# KMO_IO_MV1_1a.net
KiCad netlist of a schematic drawn in EAGLE
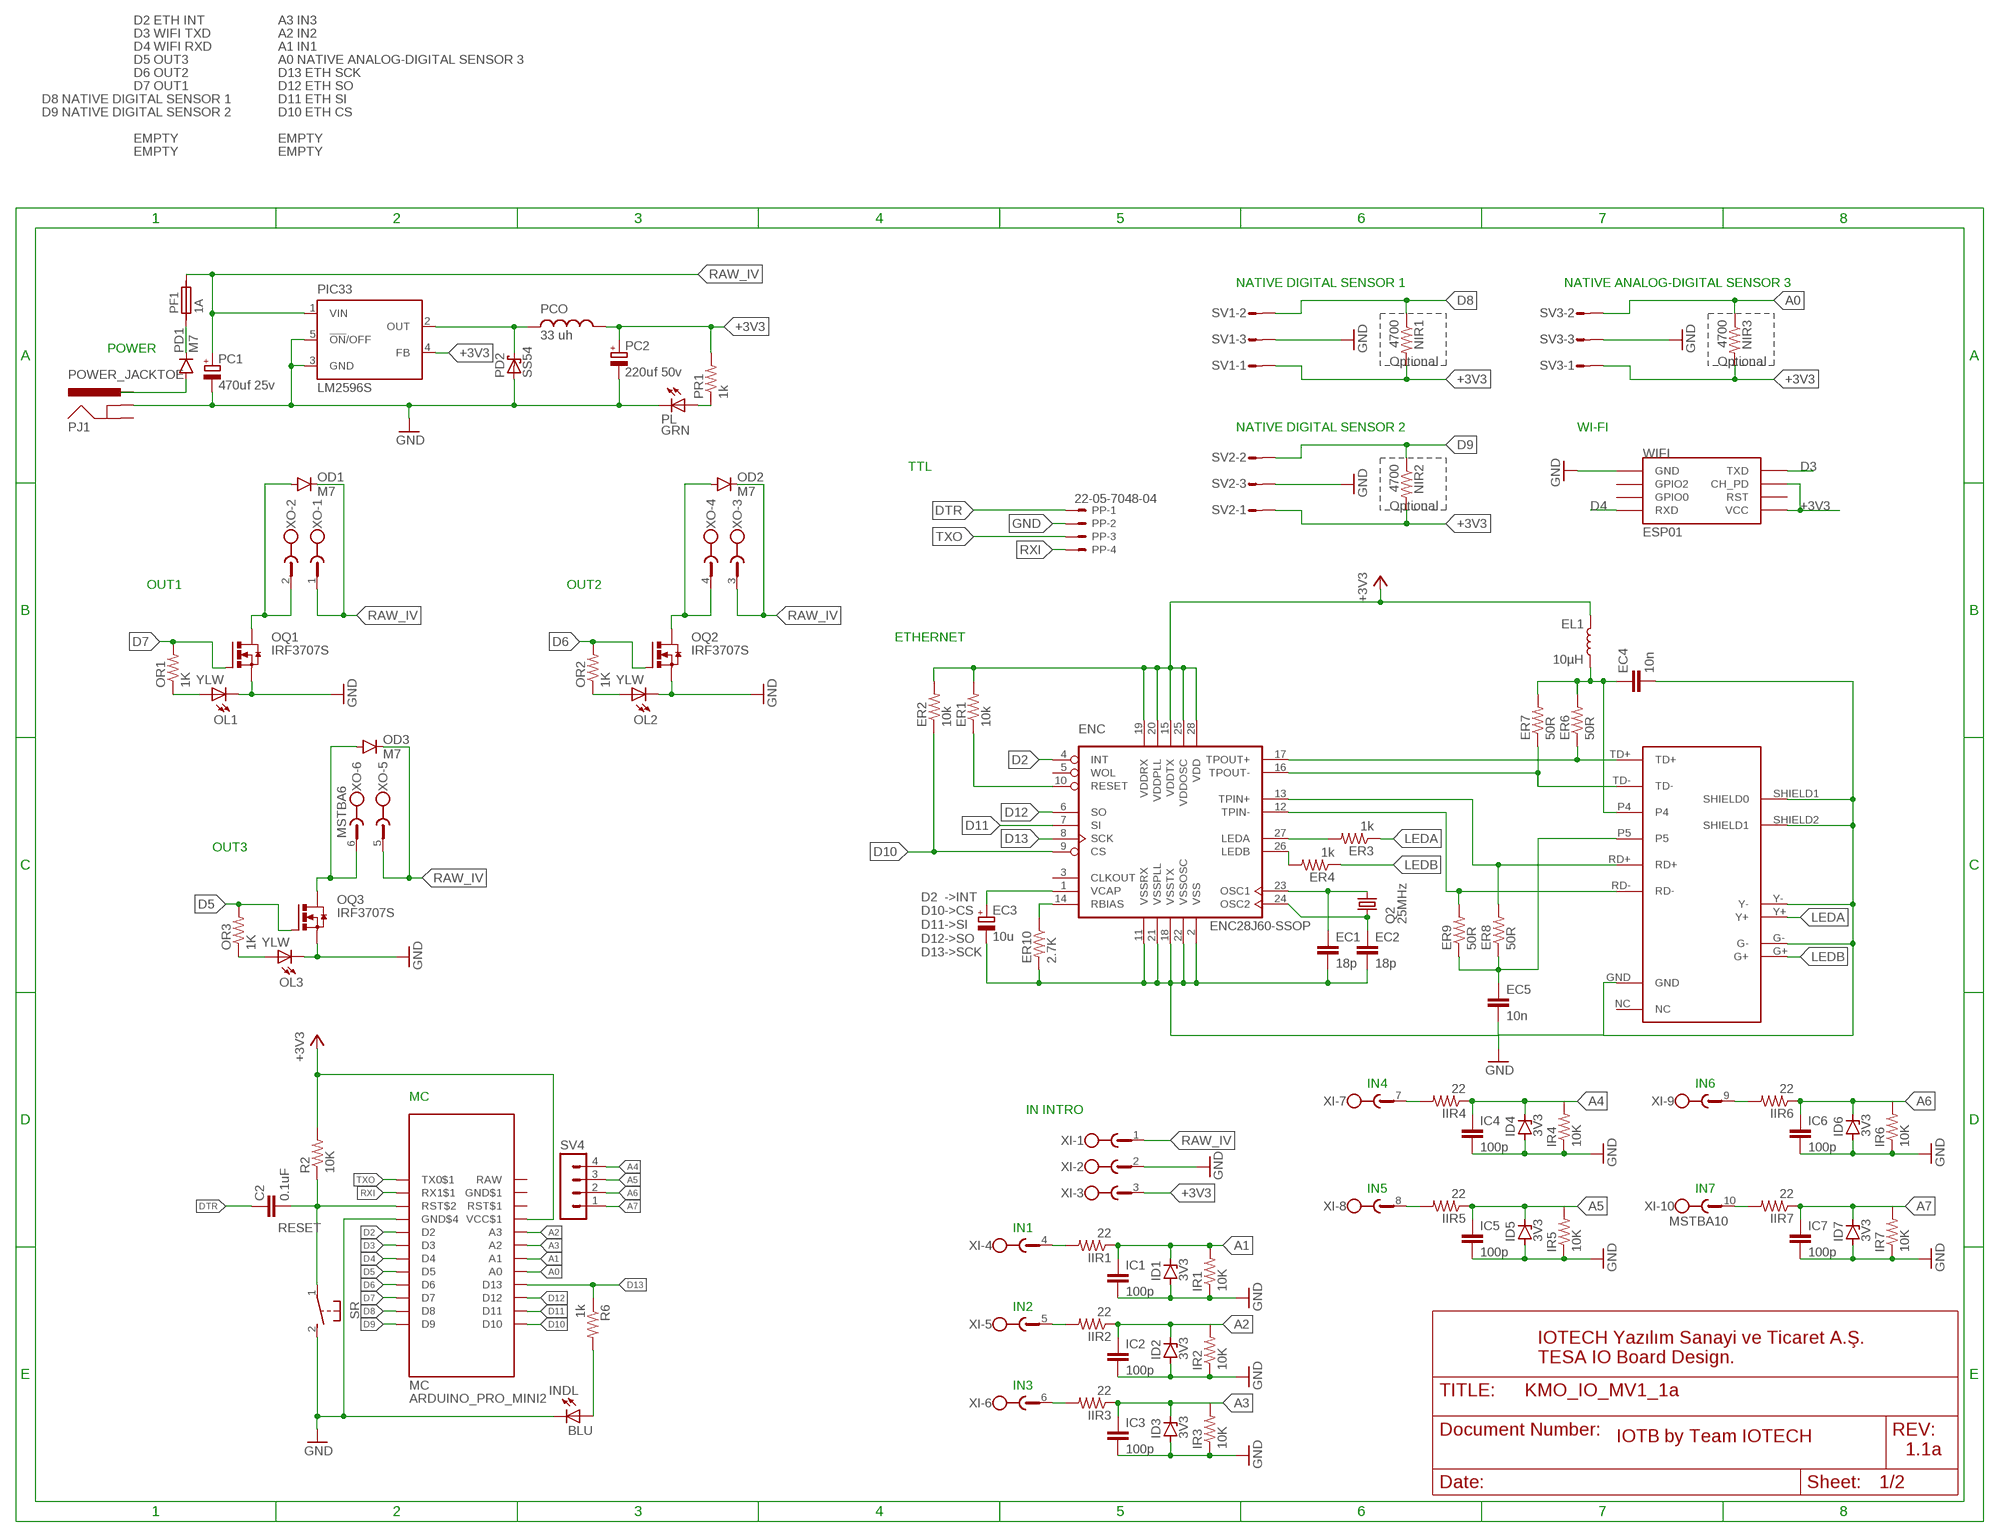
[diagram p0: schematic, sheet 1]
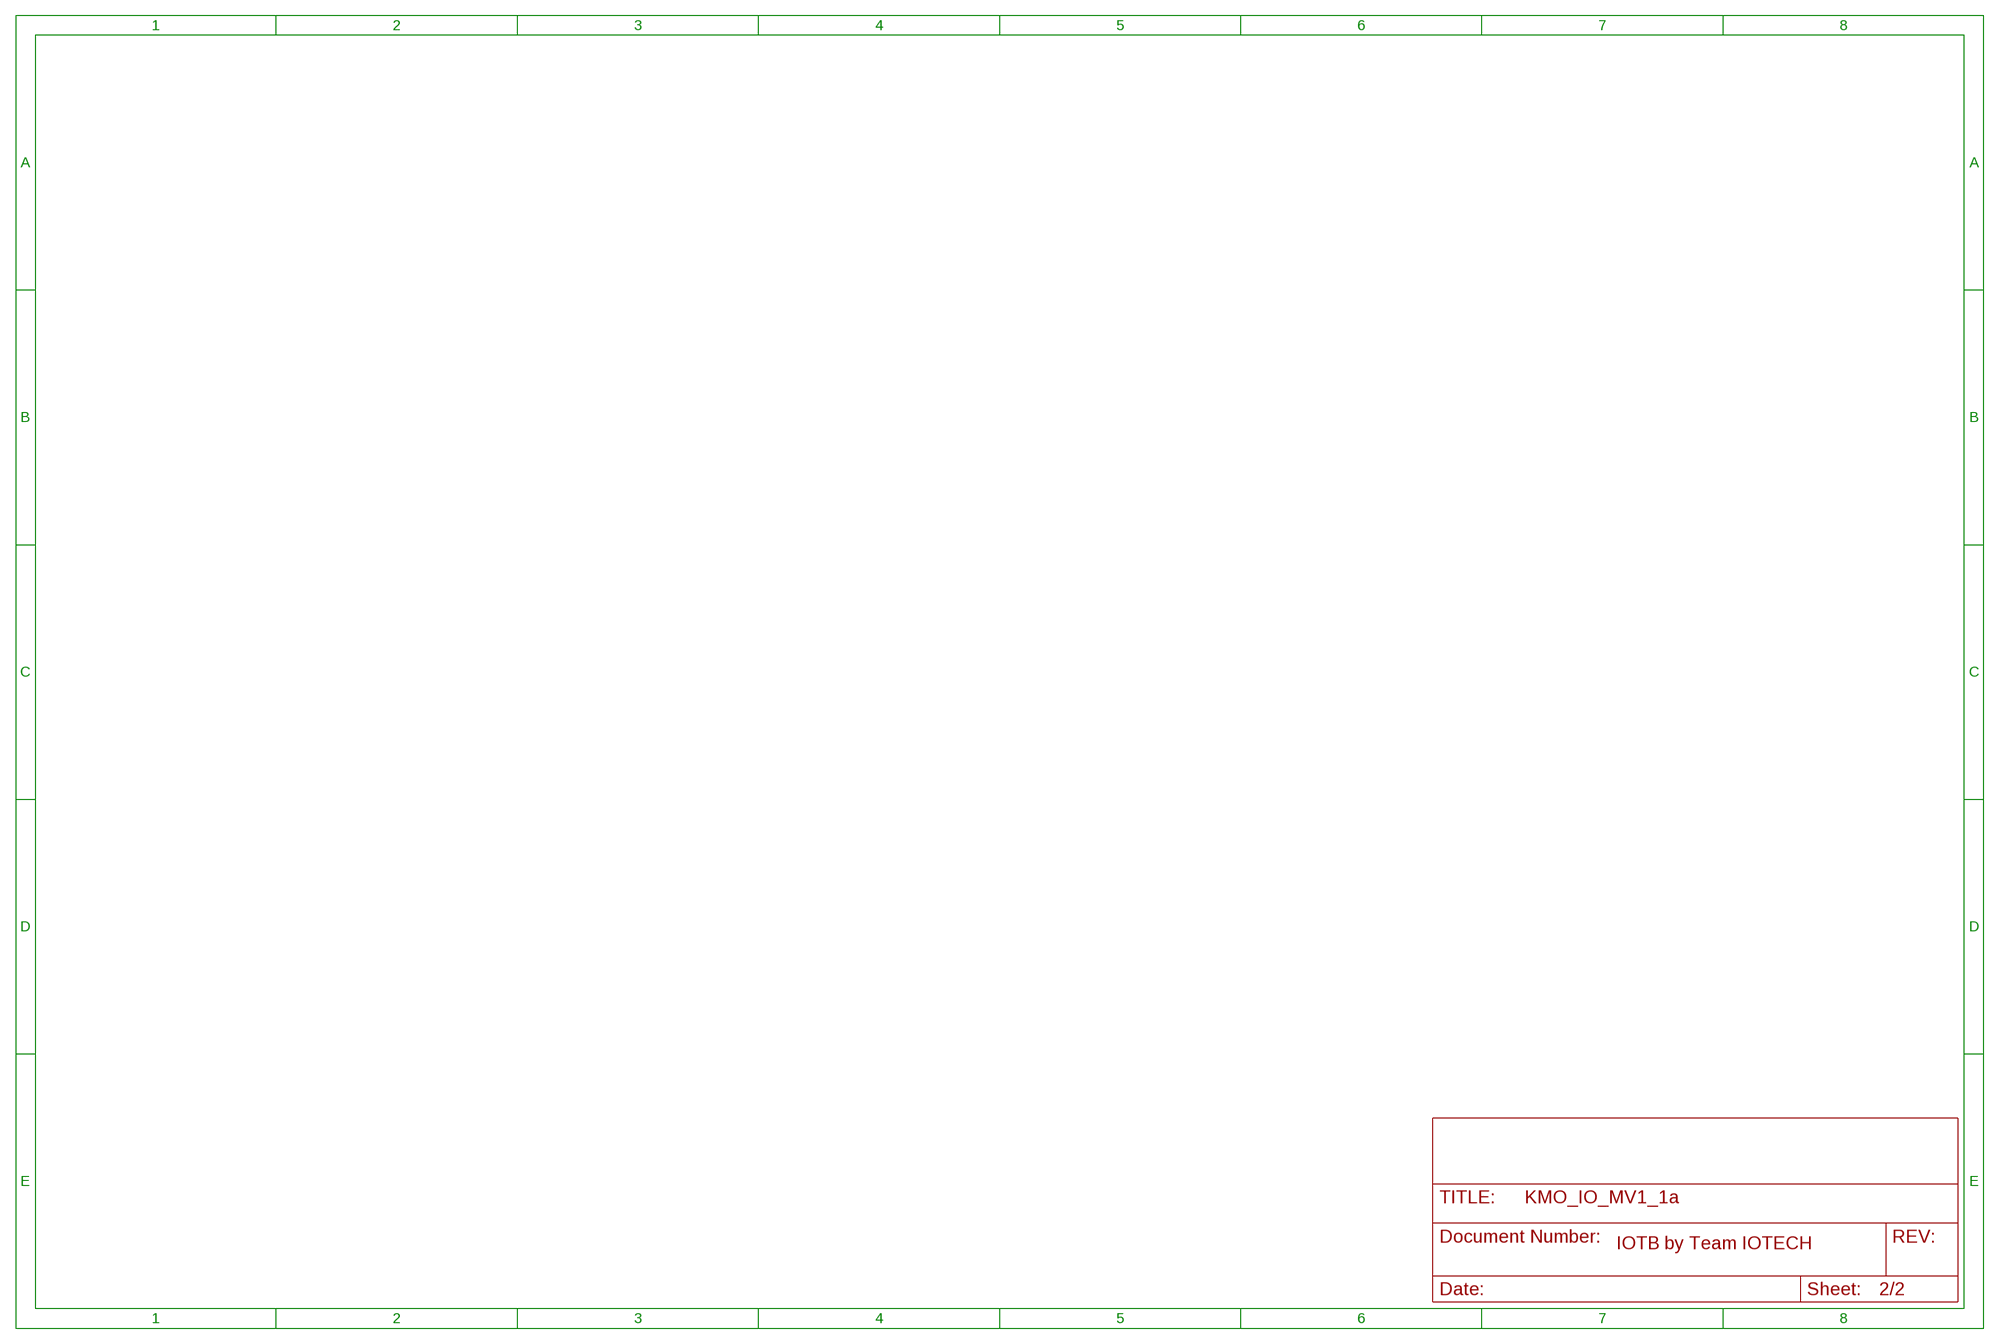
[diagram p1: schematic, sheet 2]

(export (version "E")
  (design (tool "Eeschema 10.0.6"))
  (components
    (comp (ref "C2")
      (value "0.1uF")
      (footprint "eagle-import:0805")
      (libsource (lib "eagle-import") (part "CAP0805"))
    )
    (comp (ref "EC1")
      (value "18p")
      (footprint "eagle-import:0805")
      (libsource (lib "eagle-import") (part "CAP0805"))
    )
    (comp (ref "EC2")
      (value "18p")
      (footprint "eagle-import:0805")
      (libsource (lib "eagle-import") (part "CAP0805"))
    )
    (comp (ref "EC3")
      (value "10u")
      (footprint "eagle-import:CT3216")
      (libsource (lib "eagle-import") (part "CPOL-EUCT3216"))
    )
    (comp (ref "EC4")
      (value "10n")
      (footprint "eagle-import:0805")
      (libsource (lib "eagle-import") (part "CAP0805"))
    )
    (comp (ref "EC5")
      (value "10n")
      (footprint "eagle-import:0805")
      (libsource (lib "eagle-import") (part "CAP0805"))
    )
    (comp (ref "EL1")
      (value "10µH")
      (footprint "eagle-import:0805")
      (libsource (lib "eagle-import") (part "INDUCTOR-0805-3.3UH"))
    )
    (comp (ref "ENC")
      (value "ENC28J60-SSOP")
      (footprint "eagle-import:SSOP28")
      (libsource (lib "eagle-import") (part "ENC28J60-SSOP"))
    )
    (comp (ref "ER1")
      (value "10k")
      (footprint "eagle-import:0805")
      (libsource (lib "eagle-import") (part "RESISTOR0805-RES"))
    )
    (comp (ref "ER2")
      (value "10k")
      (footprint "eagle-import:0805")
      (libsource (lib "eagle-import") (part "RESISTOR0805-RES"))
    )
    (comp (ref "ER3")
      (value "1k")
      (footprint "eagle-import:0805")
      (libsource (lib "eagle-import") (part "RESISTOR0805-RES"))
    )
    (comp (ref "ER4")
      (value "1k")
      (footprint "eagle-import:0805")
      (libsource (lib "eagle-import") (part "RESISTOR0805-RES"))
    )
    (comp (ref "ER6")
      (value "50R")
      (footprint "eagle-import:0805")
      (libsource (lib "eagle-import") (part "RESISTOR0805-RES"))
    )
    (comp (ref "ER7")
      (value "50R")
      (footprint "eagle-import:0805")
      (libsource (lib "eagle-import") (part "RESISTOR0805-RES"))
    )
    (comp (ref "ER8")
      (value "50R")
      (footprint "eagle-import:0805")
      (libsource (lib "eagle-import") (part "RESISTOR0805-RES"))
    )
    (comp (ref "ER9")
      (value "50R")
      (footprint "eagle-import:0805")
      (libsource (lib "eagle-import") (part "RESISTOR0805-RES"))
    )
    (comp (ref "ER10")
      (value "2.7K")
      (footprint "eagle-import:0805")
      (libsource (lib "eagle-import") (part "RESISTOR0805-RES"))
    )
    (comp (ref "IC1")
      (value "100p")
      (footprint "eagle-import:0805")
      (libsource (lib "eagle-import") (part "CAP0805"))
    )
    (comp (ref "IC2")
      (value "100p")
      (footprint "eagle-import:0805")
      (libsource (lib "eagle-import") (part "CAP0805"))
    )
    (comp (ref "IC3")
      (value "100p")
      (footprint "eagle-import:0805")
      (libsource (lib "eagle-import") (part "CAP0805"))
    )
    (comp (ref "IC4")
      (value "100p")
      (footprint "eagle-import:0805")
      (libsource (lib "eagle-import") (part "CAP0805"))
    )
    (comp (ref "IC5")
      (value "100p")
      (footprint "eagle-import:0805")
      (libsource (lib "eagle-import") (part "CAP0805"))
    )
    (comp (ref "IC6")
      (value "100p")
      (footprint "eagle-import:0805")
      (libsource (lib "eagle-import") (part "CAP0805"))
    )
    (comp (ref "IC7")
      (value "100p")
      (footprint "eagle-import:0805")
      (libsource (lib "eagle-import") (part "CAP0805"))
    )
    (comp (ref "ID1")
      (value "3V3")
      (footprint "eagle-import:SOT23")
      (libsource (lib "eagle-import") (part "ZENER-DIODESOT23"))
    )
    (comp (ref "ID2")
      (value "3V3")
      (footprint "eagle-import:SOT23")
      (libsource (lib "eagle-import") (part "ZENER-DIODESOT23"))
    )
    (comp (ref "ID3")
      (value "3V3")
      (footprint "eagle-import:SOT23")
      (libsource (lib "eagle-import") (part "ZENER-DIODESOT23"))
    )
    (comp (ref "ID4")
      (value "3V3")
      (footprint "eagle-import:SOT23")
      (libsource (lib "eagle-import") (part "ZENER-DIODESOT23"))
    )
    (comp (ref "ID5")
      (value "3V3")
      (footprint "eagle-import:SOT23")
      (libsource (lib "eagle-import") (part "ZENER-DIODESOT23"))
    )
    (comp (ref "ID6")
      (value "3V3")
      (footprint "eagle-import:SOT23")
      (libsource (lib "eagle-import") (part "ZENER-DIODESOT23"))
    )
    (comp (ref "ID7")
      (value "3V3")
      (footprint "eagle-import:SOT23")
      (libsource (lib "eagle-import") (part "ZENER-DIODESOT23"))
    )
    (comp (ref "IIR1")
      (value "22")
      (footprint "eagle-import:0805")
      (libsource (lib "eagle-import") (part "RESISTOR0805-RES"))
    )
    (comp (ref "IIR2")
      (value "22")
      (footprint "eagle-import:0805")
      (libsource (lib "eagle-import") (part "RESISTOR0805-RES"))
    )
    (comp (ref "IIR3")
      (value "22")
      (footprint "eagle-import:0805")
      (libsource (lib "eagle-import") (part "RESISTOR0805-RES"))
    )
    (comp (ref "IIR4")
      (value "22")
      (footprint "eagle-import:0805")
      (libsource (lib "eagle-import") (part "RESISTOR0805-RES"))
    )
    (comp (ref "IIR5")
      (value "22")
      (footprint "eagle-import:0805")
      (libsource (lib "eagle-import") (part "RESISTOR0805-RES"))
    )
    (comp (ref "IIR6")
      (value "22")
      (footprint "eagle-import:0805")
      (libsource (lib "eagle-import") (part "RESISTOR0805-RES"))
    )
    (comp (ref "IIR7")
      (value "22")
      (footprint "eagle-import:0805")
      (libsource (lib "eagle-import") (part "RESISTOR0805-RES"))
    )
    (comp (ref "INDL")
      (value "BLU")
      (footprint "eagle-import:CHIP-LED0805")
      (libsource (lib "eagle-import") (part "LEDCHIP-LED0805"))
    )
    (comp (ref "IR1")
      (value "10K")
      (footprint "eagle-import:0805")
      (libsource (lib "eagle-import") (part "RESISTOR0805-RES"))
    )
    (comp (ref "IR2")
      (value "10K")
      (footprint "eagle-import:0805")
      (libsource (lib "eagle-import") (part "RESISTOR0805-RES"))
    )
    (comp (ref "IR3")
      (value "10K")
      (footprint "eagle-import:0805")
      (libsource (lib "eagle-import") (part "RESISTOR0805-RES"))
    )
    (comp (ref "IR4")
      (value "10K")
      (footprint "eagle-import:0805")
      (libsource (lib "eagle-import") (part "RESISTOR0805-RES"))
    )
    (comp (ref "IR5")
      (value "10K")
      (footprint "eagle-import:0805")
      (libsource (lib "eagle-import") (part "RESISTOR0805-RES"))
    )
    (comp (ref "IR6")
      (value "10K")
      (footprint "eagle-import:0805")
      (libsource (lib "eagle-import") (part "RESISTOR0805-RES"))
    )
    (comp (ref "IR7")
      (value "10K")
      (footprint "eagle-import:0805")
      (libsource (lib "eagle-import") (part "RESISTOR0805-RES"))
    )
    (comp (ref "MC")
      (value "ARDUINO_PRO_MINI2")
      (footprint "eagle-import:ARDUINO_PRO_MINI2")
      (libsource (lib "eagle-import") (part "ARDUINO_PRO_MINI2"))
    )
    (comp (ref "NIR1")
      (value "4700")
      (footprint "eagle-import:0805")
      (libsource (lib "eagle-import") (part "RESISTOR0805-RES"))
    )
    (comp (ref "NIR2")
      (value "4700")
      (footprint "eagle-import:0805")
      (libsource (lib "eagle-import") (part "RESISTOR0805-RES"))
    )
    (comp (ref "NIR3")
      (value "4700")
      (footprint "eagle-import:0805")
      (libsource (lib "eagle-import") (part "RESISTOR0805-RES"))
    )
    (comp (ref "OD1")
      (value "M7")
      (footprint "eagle-import:SMA-DIODE")
      (libsource (lib "eagle-import") (part "DIODESMA"))
    )
    (comp (ref "OD2")
      (value "M7")
      (footprint "eagle-import:SMA-DIODE")
      (libsource (lib "eagle-import") (part "DIODESMA"))
    )
    (comp (ref "OD3")
      (value "M7")
      (footprint "eagle-import:SMA-DIODE")
      (libsource (lib "eagle-import") (part "DIODESMA"))
    )
    (comp (ref "OL1")
      (value "YLW")
      (footprint "eagle-import:CHIP-LED0805")
      (libsource (lib "eagle-import") (part "LEDCHIP-LED0805"))
    )
    (comp (ref "OL2")
      (value "YLW")
      (footprint "eagle-import:CHIP-LED0805")
      (libsource (lib "eagle-import") (part "LEDCHIP-LED0805"))
    )
    (comp (ref "OL3")
      (value "YLW")
      (footprint "eagle-import:CHIP-LED0805")
      (libsource (lib "eagle-import") (part "LEDCHIP-LED0805"))
    )
    (comp (ref "OQ1")
      (value "IRF3707S")
      (footprint "eagle-import:D2PACK")
      (libsource (lib "eagle-import") (part "IRF3704S"))
    )
    (comp (ref "OQ2")
      (value "IRF3707S")
      (footprint "eagle-import:D2PACK")
      (libsource (lib "eagle-import") (part "IRF3704S"))
    )
    (comp (ref "OQ3")
      (value "IRF3707S")
      (footprint "eagle-import:D2PACK")
      (libsource (lib "eagle-import") (part "IRF3704S"))
    )
    (comp (ref "OR1")
      (value "1K")
      (footprint "eagle-import:0805")
      (libsource (lib "eagle-import") (part "RESISTOR0805-RES"))
    )
    (comp (ref "OR2")
      (value "1K")
      (footprint "eagle-import:0805")
      (libsource (lib "eagle-import") (part "RESISTOR0805-RES"))
    )
    (comp (ref "OR3")
      (value "1K")
      (footprint "eagle-import:0805")
      (libsource (lib "eagle-import") (part "RESISTOR0805-RES"))
    )
    (comp (ref "PC1")
      (value "470uf 25v")
      (footprint "eagle-import:140CLH-1010")
      (libsource (lib "eagle-import") (part "CPOL-EU140CLH-1010"))
    )
    (comp (ref "PC2")
      (value "220uf 50v")
      (footprint "eagle-import:140CLH-1010")
      (libsource (lib "eagle-import") (part "CPOL-EU140CLH-1010"))
    )
    (comp (ref "PCO")
      (value "33 uh")
      (footprint "eagle-import:MSS1260")
      (libsource (lib "eagle-import") (part "MSS1260"))
    )
    (comp (ref "PD1")
      (value "M7")
      (footprint "eagle-import:SMA-DIODE")
      (libsource (lib "eagle-import") (part "DIODESMA"))
    )
    (comp (ref "PD2")
      (value "SS54")
      (footprint "eagle-import:SMB")
      (libsource (lib "eagle-import") (part "SCHOTTKY-DIODESMD"))
    )
    (comp (ref "PF1")
      (value "1A")
      (footprint "eagle-import:1820")
      (libsource (lib "eagle-import") (part "SIBA194600"))
    )
    (comp (ref "PIC33")
      (value "LM2596S")
      (footprint "eagle-import:TO263-5")
      (fields (field (name "MF") "NATIONAL SEMICONDUCTOR") (field (name "MPN") "LM2596S-ADJ/NOPB"))
      (libsource (lib "eagle-import") (part "LM2596S"))
    )
    (comp (ref "PJ1")
      (value "POWER_JACKTOE")
      (footprint "eagle-import:POWER_JACK_SMD_OVERPASTE_TOE")
      (libsource (lib "eagle-import") (part "POWER_JACKTOE"))
    )
    (comp (ref "PL")
      (value "GRN")
      (footprint "eagle-import:CHIP-LED0805")
      (libsource (lib "eagle-import") (part "LEDCHIP-LED0805"))
    )
    (comp (ref "PP")
      (value "22-05-7048-04")
      (footprint "eagle-import:7395-04")
      (fields (field (name "MF") "MOLEX"))
      (libsource (lib "eagle-import") (part "22-?-0405-7048"))
    )
    (comp (ref "PR1")
      (value "1k")
      (footprint "eagle-import:0805")
      (libsource (lib "eagle-import") (part "RESISTOR0805-RES"))
    )
    (comp (ref "Q2")
      (value "25MHz")
      (footprint "eagle-import:5.0X3.2_2")
      (libsource (lib "eagle-import") (part "KX-9B"))
    )
    (comp (ref "R2")
      (value "10K")
      (footprint "eagle-import:0805")
      (libsource (lib "eagle-import") (part "RESISTOR0805-RES"))
    )
    (comp (ref "R6")
      (value "1k")
      (footprint "eagle-import:0805")
      (libsource (lib "eagle-import") (part "RESISTOR0805-RES"))
    )
    (comp (ref "SR")
      (value "31-XX")
      (footprint "eagle-import:B3F-31XX")
      (fields (field (name "MPN") "B3F-3100"))
      (libsource (lib "eagle-import") (part "31-XX"))
    )
    (comp (ref "SV1")
      (value "S03P")
      (footprint "eagle-import:S03P")
      (libsource (lib "eagle-import") (part "S03P"))
    )
    (comp (ref "SV2")
      (value "S03P")
      (footprint "eagle-import:S03P")
      (libsource (lib "eagle-import") (part "S03P"))
    )
    (comp (ref "SV3")
      (value "S03P")
      (footprint "eagle-import:S03P")
      (libsource (lib "eagle-import") (part "S03P"))
    )
    (comp (ref "SV4")
      (value "MA04-1")
      (footprint "eagle-import:MA04-1")
      (libsource (lib "eagle-import") (part "MA04-1"))
    )
    (comp (ref "U$2")
      (value "HR911105A")
      (footprint "eagle-import:RJ45")
      (libsource (lib "eagle-import") (part "HR911105A"))
    )
    (comp (ref "WIFI")
      (value "ESP01")
      (footprint "eagle-import:ESP01")
      (libsource (lib "eagle-import") (part "ESP01"))
    )
    (comp (ref "XI")
      (value "MSTBA10")
      (footprint "eagle-import:MSTBA10")
      (fields (field (name "MF") "FARNELL") (field (name "MPN") "1757323"))
      (libsource (lib "eagle-import") (part "MSTBA10"))
    )
    (comp (ref "XO")
      (value "MSTBA6")
      (footprint "eagle-import:MSTBA6")
      (fields (field (name "MF") "FARNELL") (field (name "MPN") "1757284"))
      (libsource (lib "eagle-import") (part "MSTBA6"))
    )
  )
  (nets
    (net (code "1") (name "+3V3") (class "Default")
      (node (ref "EL1") (pin "1") (pinfunction "1_1") (pintype "passive"))
      (node (ref "ENC") (pin "15") (pinfunction "VDDTX_15") (pintype "power_in"))
      (node (ref "ENC") (pin "19") (pinfunction "VDDRX_19") (pintype "power_in"))
      (node (ref "ENC") (pin "20") (pinfunction "VDDPLL_20") (pintype "power_in"))
      (node (ref "ENC") (pin "25") (pinfunction "VDDOSC_25") (pintype "power_in"))
      (node (ref "ENC") (pin "28") (pinfunction "VDD_28") (pintype "power_in"))
      (node (ref "ER1") (pin "2") (pinfunction "2_2") (pintype "passive"))
      (node (ref "ER2") (pin "2") (pinfunction "2_2") (pintype "passive"))
      (node (ref "MC") (pin "VCC$1") (pinfunction "VCC$1_VCC$1") (pintype "power_in"))
      (node (ref "NIR1") (pin "2") (pinfunction "2_2") (pintype "passive"))
      (node (ref "NIR2") (pin "2") (pinfunction "2_2") (pintype "passive"))
      (node (ref "NIR3") (pin "2") (pinfunction "2_2") (pintype "passive"))
      (node (ref "PC2") (pin "+") (pinfunction "+_+") (pintype "passive"))
      (node (ref "PCO") (pin "P$1") (pinfunction "P$1_P$1") (pintype "passive"))
      (node (ref "PIC33") (pin "4") (pinfunction "FB_4") (pintype "input"))
      (node (ref "PR1") (pin "2") (pinfunction "2_2") (pintype "passive"))
      (node (ref "R2") (pin "2") (pinfunction "2_2") (pintype "passive"))
      (node (ref "SV1") (pin "1") (pinfunction "S_1") (pintype "passive"))
      (node (ref "SV2") (pin "1") (pinfunction "S_1") (pintype "passive"))
      (node (ref "SV3") (pin "1") (pinfunction "S_1") (pintype "passive"))
      (node (ref "WIFI") (pin "CH_PD") (pinfunction "CH_PD_CH_PD") (pintype "bidirectional"))
      (node (ref "WIFI") (pin "VCC") (pinfunction "VCC_VCC") (pintype "bidirectional"))
      (node (ref "XI") (pin "3") (pinfunction "1_3") (pintype "passive"))
    )
    (net (code "2") (name "A0") (class "Default")
      (node (ref "MC") (pin "A0") (pinfunction "A0_A0") (pintype "bidirectional"))
      (node (ref "NIR3") (pin "1") (pinfunction "1_1") (pintype "passive"))
      (node (ref "SV3") (pin "2") (pinfunction "S_2") (pintype "passive"))
    )
    (net (code "3") (name "A1") (class "Default")
      (node (ref "IC1") (pin "1") (pinfunction "1_1") (pintype "passive"))
      (node (ref "ID1") (pin "3") (pinfunction "C_3") (pintype "passive"))
      (node (ref "IIR1") (pin "1") (pinfunction "1_1") (pintype "passive"))
      (node (ref "IR1") (pin "2") (pinfunction "2_2") (pintype "passive"))
      (node (ref "MC") (pin "A1") (pinfunction "A1_A1") (pintype "bidirectional"))
    )
    (net (code "4") (name "A2") (class "Default")
      (node (ref "IC2") (pin "1") (pinfunction "1_1") (pintype "passive"))
      (node (ref "ID2") (pin "3") (pinfunction "C_3") (pintype "passive"))
      (node (ref "IIR2") (pin "1") (pinfunction "1_1") (pintype "passive"))
      (node (ref "IR2") (pin "2") (pinfunction "2_2") (pintype "passive"))
      (node (ref "MC") (pin "A3") (pinfunction "A3_A3") (pintype "bidirectional"))
    )
    (net (code "5") (name "A3") (class "Default")
      (node (ref "IC3") (pin "1") (pinfunction "1_1") (pintype "passive"))
      (node (ref "ID3") (pin "3") (pinfunction "C_3") (pintype "passive"))
      (node (ref "IIR3") (pin "1") (pinfunction "1_1") (pintype "passive"))
      (node (ref "IR3") (pin "2") (pinfunction "2_2") (pintype "passive"))
      (node (ref "MC") (pin "A2") (pinfunction "A2_A2") (pintype "bidirectional"))
    )
    (net (code "6") (name "A4") (class "Default")
      (node (ref "IC4") (pin "1") (pinfunction "1_1") (pintype "passive"))
      (node (ref "ID4") (pin "3") (pinfunction "C_3") (pintype "passive"))
      (node (ref "IIR4") (pin "1") (pinfunction "1_1") (pintype "passive"))
      (node (ref "IR4") (pin "2") (pinfunction "2_2") (pintype "passive"))
      (node (ref "SV4") (pin "4") (pinfunction "4_4") (pintype "passive"))
    )
    (net (code "7") (name "A5") (class "Default")
      (node (ref "IC5") (pin "1") (pinfunction "1_1") (pintype "passive"))
      (node (ref "ID5") (pin "3") (pinfunction "C_3") (pintype "passive"))
      (node (ref "IIR5") (pin "1") (pinfunction "1_1") (pintype "passive"))
      (node (ref "IR5") (pin "2") (pinfunction "2_2") (pintype "passive"))
      (node (ref "SV4") (pin "3") (pinfunction "3_3") (pintype "passive"))
    )
    (net (code "8") (name "A6") (class "Default")
      (node (ref "IC6") (pin "1") (pinfunction "1_1") (pintype "passive"))
      (node (ref "ID6") (pin "3") (pinfunction "C_3") (pintype "passive"))
      (node (ref "IIR6") (pin "1") (pinfunction "1_1") (pintype "passive"))
      (node (ref "IR6") (pin "2") (pinfunction "2_2") (pintype "passive"))
      (node (ref "SV4") (pin "2") (pinfunction "2_2") (pintype "passive"))
    )
    (net (code "9") (name "A7") (class "Default")
      (node (ref "IC7") (pin "1") (pinfunction "1_1") (pintype "passive"))
      (node (ref "ID7") (pin "3") (pinfunction "C_3") (pintype "passive"))
      (node (ref "IIR7") (pin "1") (pinfunction "1_1") (pintype "passive"))
      (node (ref "IR7") (pin "2") (pinfunction "2_2") (pintype "passive"))
      (node (ref "SV4") (pin "1") (pinfunction "1_1") (pintype "passive"))
    )
    (net (code "10") (name "D2") (class "Default")
      (node (ref "ENC") (pin "4") (pinfunction "INT_4") (pintype "output"))
      (node (ref "MC") (pin "D2") (pinfunction "D2_D2") (pintype "bidirectional"))
    )
    (net (code "11") (name "D3") (class "Default")
      (node (ref "MC") (pin "D3") (pinfunction "D3_D3") (pintype "bidirectional"))
      (node (ref "WIFI") (pin "TX") (pinfunction "TXD_TX") (pintype "bidirectional"))
    )
    (net (code "12") (name "D4") (class "Default")
      (node (ref "MC") (pin "D4") (pinfunction "D4_D4") (pintype "bidirectional"))
      (node (ref "WIFI") (pin "RX") (pinfunction "RXD_RX") (pintype "bidirectional"))
    )
    (net (code "13") (name "D5") (class "Default")
      (node (ref "MC") (pin "D5") (pinfunction "D5_D5") (pintype "bidirectional"))
      (node (ref "OQ3") (pin "1") (pinfunction "G_1") (pintype "passive"))
      (node (ref "OR3") (pin "2") (pinfunction "2_2") (pintype "passive"))
    )
    (net (code "14") (name "D6") (class "Default")
      (node (ref "MC") (pin "D6") (pinfunction "D6_D6") (pintype "bidirectional"))
      (node (ref "OQ2") (pin "1") (pinfunction "G_1") (pintype "passive"))
      (node (ref "OR2") (pin "2") (pinfunction "2_2") (pintype "passive"))
    )
    (net (code "15") (name "D7") (class "Default")
      (node (ref "MC") (pin "D7") (pinfunction "D7_D7") (pintype "bidirectional"))
      (node (ref "OQ1") (pin "1") (pinfunction "G_1") (pintype "passive"))
      (node (ref "OR1") (pin "2") (pinfunction "2_2") (pintype "passive"))
    )
    (net (code "16") (name "D8") (class "Default")
      (node (ref "MC") (pin "D8") (pinfunction "D8_D8") (pintype "bidirectional"))
      (node (ref "NIR1") (pin "1") (pinfunction "1_1") (pintype "passive"))
      (node (ref "SV1") (pin "2") (pinfunction "S_2") (pintype "passive"))
    )
    (net (code "17") (name "D9") (class "Default")
      (node (ref "MC") (pin "D9") (pinfunction "D9_D9") (pintype "bidirectional"))
      (node (ref "NIR2") (pin "1") (pinfunction "1_1") (pintype "passive"))
      (node (ref "SV2") (pin "2") (pinfunction "S_2") (pintype "passive"))
    )
    (net (code "18") (name "D10") (class "Default")
      (node (ref "ENC") (pin "9") (pinfunction "CS_9") (pintype "input"))
      (node (ref "ER2") (pin "1") (pinfunction "1_1") (pintype "passive"))
      (node (ref "MC") (pin "D10") (pinfunction "D10_D10") (pintype "bidirectional"))
    )
    (net (code "19") (name "D11") (class "Default")
      (node (ref "ENC") (pin "7") (pinfunction "SI_7") (pintype "input"))
      (node (ref "MC") (pin "D11") (pinfunction "D11_D11") (pintype "bidirectional"))
    )
    (net (code "20") (name "D12") (class "Default")
      (node (ref "ENC") (pin "6") (pinfunction "SO_6") (pintype "output"))
      (node (ref "MC") (pin "D12") (pinfunction "D12_D12") (pintype "bidirectional"))
    )
    (net (code "21") (name "D13") (class "Default")
      (node (ref "ENC") (pin "8") (pinfunction "SCK_8") (pintype "input"))
      (node (ref "MC") (pin "D13") (pinfunction "D13_D13") (pintype "bidirectional"))
      (node (ref "R6") (pin "1") (pinfunction "1_1") (pintype "passive"))
    )
    (net (code "22") (name "DTR") (class "Default")
      (node (ref "C2") (pin "2") (pinfunction "2_2") (pintype "passive"))
      (node (ref "PP") (pin "1") (pinfunction "S_1") (pintype "passive"))
    )
    (net (code "23") (name "GND") (class "Default")
      (node (ref "EC1") (pin "2") (pinfunction "2_2") (pintype "passive"))
      (node (ref "EC2") (pin "2") (pinfunction "2_2") (pintype "passive"))
      (node (ref "EC3") (pin "-") (pinfunction "-_-") (pintype "passive"))
      (node (ref "EC4") (pin "2") (pinfunction "2_2") (pintype "passive"))
      (node (ref "EC5") (pin "2") (pinfunction "2_2") (pintype "passive"))
      (node (ref "ENC") (pin "11") (pinfunction "VSSRX_11") (pintype "power_in"))
      (node (ref "ENC") (pin "18") (pinfunction "VSSTX_18") (pintype "power_in"))
      (node (ref "ENC") (pin "2") (pinfunction "VSS_2") (pintype "power_in"))
      (node (ref "ENC") (pin "21") (pinfunction "VSSPLL_21") (pintype "power_in"))
      (node (ref "ENC") (pin "22") (pinfunction "VSSOSC_22") (pintype "power_in"))
      (node (ref "ER10") (pin "2") (pinfunction "2_2") (pintype "passive"))
      (node (ref "IC1") (pin "2") (pinfunction "2_2") (pintype "passive"))
      (node (ref "IC2") (pin "2") (pinfunction "2_2") (pintype "passive"))
      (node (ref "IC3") (pin "2") (pinfunction "2_2") (pintype "passive"))
      (node (ref "IC4") (pin "2") (pinfunction "2_2") (pintype "passive"))
      (node (ref "IC5") (pin "2") (pinfunction "2_2") (pintype "passive"))
      (node (ref "IC6") (pin "2") (pinfunction "2_2") (pintype "passive"))
      (node (ref "IC7") (pin "2") (pinfunction "2_2") (pintype "passive"))
      (node (ref "ID1") (pin "1") (pinfunction "A_1") (pintype "passive"))
      (node (ref "ID2") (pin "1") (pinfunction "A_1") (pintype "passive"))
      (node (ref "ID3") (pin "1") (pinfunction "A_1") (pintype "passive"))
      (node (ref "ID4") (pin "1") (pinfunction "A_1") (pintype "passive"))
      (node (ref "ID5") (pin "1") (pinfunction "A_1") (pintype "passive"))
      (node (ref "ID6") (pin "1") (pinfunction "A_1") (pintype "passive"))
      (node (ref "ID7") (pin "1") (pinfunction "A_1") (pintype "passive"))
      (node (ref "INDL") (pin "C") (pinfunction "C_C") (pintype "passive"))
      (node (ref "IR1") (pin "1") (pinfunction "1_1") (pintype "passive"))
      (node (ref "IR2") (pin "1") (pinfunction "1_1") (pintype "passive"))
      (node (ref "IR3") (pin "1") (pinfunction "1_1") (pintype "passive"))
      (node (ref "IR4") (pin "1") (pinfunction "1_1") (pintype "passive"))
      (node (ref "IR5") (pin "1") (pinfunction "1_1") (pintype "passive"))
      (node (ref "IR6") (pin "1") (pinfunction "1_1") (pintype "passive"))
      (node (ref "IR7") (pin "1") (pinfunction "1_1") (pintype "passive"))
      (node (ref "MC") (pin "GND$4") (pinfunction "GND$4_GND$4") (pintype "power_in"))
      (node (ref "OL1") (pin "C") (pinfunction "C_C") (pintype "passive"))
      (node (ref "OL2") (pin "C") (pinfunction "C_C") (pintype "passive"))
      (node (ref "OL3") (pin "C") (pinfunction "C_C") (pintype "passive"))
      (node (ref "OQ1") (pin "3") (pinfunction "S_3") (pintype "passive"))
      (node (ref "OQ2") (pin "3") (pinfunction "S_3") (pintype "passive"))
      (node (ref "OQ3") (pin "3") (pinfunction "S_3") (pintype "passive"))
      (node (ref "PC1") (pin "-") (pinfunction "-_-") (pintype "passive"))
      (node (ref "PC2") (pin "-") (pinfunction "-_-") (pintype "passive"))
      (node (ref "PD2") (pin "A") (pinfunction "A_A") (pintype "passive"))
      (node (ref "PIC33") (pin "3") (pinfunction "GND_3") (pintype "power_in"))
      (node (ref "PIC33") (pin "5") (pinfunction "~{ON}/OFF_5") (pintype "input"))
      (node (ref "PJ1") (pin "GND") (pinfunction "GNDBREAK_GND") (pintype "bidirectional"))
      (node (ref "PL") (pin "C") (pinfunction "C_C") (pintype "passive"))
      (node (ref "PP") (pin "2") (pinfunction "S_2") (pintype "passive"))
      (node (ref "SR") (pin "2") (pinfunction "S_2") (pintype "passive"))
      (node (ref "SV1") (pin "3") (pinfunction "S_3") (pintype "passive"))
      (node (ref "SV2") (pin "3") (pinfunction "S_3") (pintype "passive"))
      (node (ref "SV3") (pin "3") (pinfunction "S_3") (pintype "passive"))
      (node (ref "U$2") (pin "G-") (pinfunction "G-_G-") (pintype "bidirectional"))
      (node (ref "U$2") (pin "GND") (pinfunction "GND_GND") (pintype "bidirectional"))
      (node (ref "U$2") (pin "SHIELD1") (pinfunction "SHIELD0_SHIELD1") (pintype "bidirectional"))
      (node (ref "U$2") (pin "SHIELD2") (pinfunction "SHIELD1_SHIELD2") (pintype "bidirectional"))
      (node (ref "U$2") (pin "Y-") (pinfunction "Y-_Y-") (pintype "bidirectional"))
      (node (ref "WIFI") (pin "GND") (pinfunction "GND_GND") (pintype "bidirectional"))
      (node (ref "XI") (pin "2") (pinfunction "1_2") (pintype "passive"))
    )
    (net (code "24") (name "GND$1") (class "Default")
      (node (ref "MC") (pin "GDN$1") (pinfunction "GND$1_GDN$1") (pintype "power_in"))
    )
    (net (code "25") (name "LEDA") (class "Default")
      (node (ref "ER3") (pin "1") (pinfunction "1_1") (pintype "passive"))
      (node (ref "U$2") (pin "Y+") (pinfunction "Y+_Y+") (pintype "bidirectional"))
    )
    (net (code "26") (name "LEDB") (class "Default")
      (node (ref "ER4") (pin "1") (pinfunction "1_1") (pintype "passive"))
      (node (ref "U$2") (pin "G+") (pinfunction "G+_G+") (pintype "bidirectional"))
    )
    (net (code "27") (name "Net-(EC4-Pad1)") (class "Default")
      (node (ref "EC4") (pin "1") (pinfunction "1_1") (pintype "passive"))
      (node (ref "EL1") (pin "2") (pinfunction "2_2") (pintype "passive"))
      (node (ref "ER6") (pin "2") (pinfunction "2_2") (pintype "passive"))
      (node (ref "ER7") (pin "2") (pinfunction "2_2") (pintype "passive"))
      (node (ref "U$2") (pin "P4") (pinfunction "P4_P4") (pintype "bidirectional"))
    )
    (net (code "28") (name "Net-(EC5-Pad1)") (class "Default")
      (node (ref "EC5") (pin "1") (pinfunction "1_1") (pintype "passive"))
      (node (ref "ER8") (pin "1") (pinfunction "1_1") (pintype "passive"))
      (node (ref "ER9") (pin "1") (pinfunction "1_1") (pintype "passive"))
      (node (ref "U$2") (pin "P5") (pinfunction "P5_P5") (pintype "bidirectional"))
    )
    (net (code "29") (name "Net-(ENC-LEDA)") (class "Default")
      (node (ref "ENC") (pin "27") (pinfunction "LEDA_27") (pintype "output"))
      (node (ref "ER3") (pin "2") (pinfunction "2_2") (pintype "passive"))
    )
    (net (code "30") (name "Net-(ENC-LEDB)") (class "Default")
      (node (ref "ENC") (pin "26") (pinfunction "LEDB_26") (pintype "output"))
      (node (ref "ER4") (pin "2") (pinfunction "2_2") (pintype "passive"))
    )
    (net (code "31") (name "Net-(ENC-OSC1)") (class "Default")
      (node (ref "EC1") (pin "1") (pinfunction "1_1") (pintype "passive"))
      (node (ref "ENC") (pin "23") (pinfunction "OSC1_23") (pintype "input"))
      (node (ref "Q2") (pin "2") (pinfunction "2_2") (pintype "passive"))
    )
    (net (code "32") (name "Net-(ENC-OSC2)") (class "Default")
      (node (ref "EC2") (pin "1") (pinfunction "1_1") (pintype "passive"))
      (node (ref "ENC") (pin "24") (pinfunction "OSC2_24") (pintype "output"))
      (node (ref "Q2") (pin "1") (pinfunction "1_1") (pintype "passive"))
    )
    (net (code "33") (name "Net-(ENC-RBIAS)") (class "Default")
      (node (ref "ENC") (pin "14") (pinfunction "RBIAS_14") (pintype "passive"))
      (node (ref "ER10") (pin "1") (pinfunction "1_1") (pintype "passive"))
    )
    (net (code "34") (name "Net-(ENC-RESET)") (class "Default")
      (node (ref "ENC") (pin "10") (pinfunction "RESET_10") (pintype "input"))
      (node (ref "ER1") (pin "1") (pinfunction "1_1") (pintype "passive"))
    )
    (net (code "35") (name "Net-(ENC-TPIN+)") (class "Default")
      (node (ref "ENC") (pin "13") (pinfunction "TPIN+_13") (pintype "input"))
      (node (ref "ER8") (pin "2") (pinfunction "2_2") (pintype "passive"))
      (node (ref "U$2") (pin "RD+") (pinfunction "RD+_RD+") (pintype "bidirectional"))
    )
    (net (code "36") (name "Net-(ENC-TPIN-)") (class "Default")
      (node (ref "ENC") (pin "12") (pinfunction "TPIN-_12") (pintype "input"))
      (node (ref "ER9") (pin "2") (pinfunction "2_2") (pintype "passive"))
      (node (ref "U$2") (pin "RD-") (pinfunction "RD-_RD-") (pintype "bidirectional"))
    )
    (net (code "37") (name "Net-(ENC-TPOUT+)") (class "Default")
      (node (ref "ENC") (pin "17") (pinfunction "TPOUT+_17") (pintype "output"))
      (node (ref "ER6") (pin "1") (pinfunction "1_1") (pintype "passive"))
      (node (ref "U$2") (pin "TD+") (pinfunction "TD+_TD+") (pintype "bidirectional"))
    )
    (net (code "38") (name "Net-(ENC-TPOUT-)") (class "Default")
      (node (ref "ENC") (pin "16") (pinfunction "TPOUT-_16") (pintype "output"))
      (node (ref "ER7") (pin "1") (pinfunction "1_1") (pintype "passive"))
      (node (ref "U$2") (pin "TD-") (pinfunction "TD-_TD-") (pintype "bidirectional"))
    )
    (net (code "39") (name "Net-(ENC-VCAP)") (class "Default")
      (node (ref "EC3") (pin "+") (pinfunction "+_+") (pintype "passive"))
      (node (ref "ENC") (pin "1") (pinfunction "VCAP_1") (pintype "power_in"))
    )
    (net (code "40") (name "Net-(INDL-PadA)") (class "Default")
      (node (ref "INDL") (pin "A") (pinfunction "A_A") (pintype "passive"))
      (node (ref "R6") (pin "2") (pinfunction "2_2") (pintype "passive"))
    )
    (net (code "41") (name "Net-(OL1-PadA)") (class "Default")
      (node (ref "OL1") (pin "A") (pinfunction "A_A") (pintype "passive"))
      (node (ref "OR1") (pin "1") (pinfunction "1_1") (pintype "passive"))
    )
    (net (code "42") (name "Net-(OL2-PadA)") (class "Default")
      (node (ref "OL2") (pin "A") (pinfunction "A_A") (pintype "passive"))
      (node (ref "OR2") (pin "1") (pinfunction "1_1") (pintype "passive"))
    )
    (net (code "43") (name "Net-(OL3-PadA)") (class "Default")
      (node (ref "OL3") (pin "A") (pinfunction "A_A") (pintype "passive"))
      (node (ref "OR3") (pin "1") (pinfunction "1_1") (pintype "passive"))
    )
    (net (code "44") (name "Net-(OQ1-D)") (class "Default")
      (node (ref "OD1") (pin "A") (pinfunction "A_A") (pintype "passive"))
      (node (ref "OQ1") (pin "2") (pinfunction "D_2") (pintype "passive"))
      (node (ref "XO") (pin "2") (pinfunction "1_2") (pintype "passive"))
    )
    (net (code "45") (name "Net-(OQ2-D)") (class "Default")
      (node (ref "OD2") (pin "A") (pinfunction "A_A") (pintype "passive"))
      (node (ref "OQ2") (pin "2") (pinfunction "D_2") (pintype "passive"))
      (node (ref "XO") (pin "4") (pinfunction "1_4") (pintype "passive"))
    )
    (net (code "46") (name "Net-(OQ3-D)") (class "Default")
      (node (ref "OD3") (pin "A") (pinfunction "A_A") (pintype "passive"))
      (node (ref "OQ3") (pin "2") (pinfunction "D_2") (pintype "passive"))
      (node (ref "XO") (pin "6") (pinfunction "1_6") (pintype "passive"))
    )
    (net (code "47") (name "Net-(PD1-PadC)") (class "Default")
      (node (ref "PD1") (pin "C") (pinfunction "C_C") (pintype "passive"))
      (node (ref "PF1") (pin "1") (pinfunction "1_1") (pintype "passive"))
    )
    (net (code "48") (name "Net-(PIC33-OUT)") (class "Default")
      (node (ref "PCO") (pin "P$2") (pinfunction "P$2_P$2") (pintype "passive"))
      (node (ref "PD2") (pin "C") (pinfunction "C_C") (pintype "passive"))
      (node (ref "PIC33") (pin "2") (pinfunction "OUT_2") (pintype "output"))
    )
    (net (code "49") (name "Net-(PJ1-PWR)") (class "Default")
      (node (ref "PD1") (pin "A") (pinfunction "A_A") (pintype "passive"))
      (node (ref "PJ1") (pin "VIN0") (pinfunction "PWR_VIN0") (pintype "bidirectional"))
    )
    (net (code "50") (name "Net-(PL-PadA)") (class "Default")
      (node (ref "PL") (pin "A") (pinfunction "A_A") (pintype "passive"))
      (node (ref "PR1") (pin "1") (pinfunction "1_1") (pintype "passive"))
    )
    (net (code "51") (name "Net-(XIB-1)") (class "Default")
      (node (ref "IIR7") (pin "2") (pinfunction "2_2") (pintype "passive"))
      (node (ref "XI") (pin "10") (pinfunction "1_10") (pintype "passive"))
    )
    (net (code "52") (name "Net-(XIE-1)") (class "Default")
      (node (ref "IIR1") (pin "2") (pinfunction "2_2") (pintype "passive"))
      (node (ref "XI") (pin "4") (pinfunction "1_4") (pintype "passive"))
    )
    (net (code "53") (name "Net-(XIF-1)") (class "Default")
      (node (ref "IIR2") (pin "2") (pinfunction "2_2") (pintype "passive"))
      (node (ref "XI") (pin "5") (pinfunction "1_5") (pintype "passive"))
    )
    (net (code "54") (name "Net-(XIG-1)") (class "Default")
      (node (ref "IIR3") (pin "2") (pinfunction "2_2") (pintype "passive"))
      (node (ref "XI") (pin "6") (pinfunction "1_6") (pintype "passive"))
    )
    (net (code "55") (name "Net-(XIH-1)") (class "Default")
      (node (ref "IIR4") (pin "2") (pinfunction "2_2") (pintype "passive"))
      (node (ref "XI") (pin "7") (pinfunction "1_7") (pintype "passive"))
    )
    (net (code "56") (name "Net-(XII-1)") (class "Default")
      (node (ref "IIR5") (pin "2") (pinfunction "2_2") (pintype "passive"))
      (node (ref "XI") (pin "8") (pinfunction "1_8") (pintype "passive"))
    )
    (net (code "57") (name "Net-(XIJ-1)") (class "Default")
      (node (ref "IIR6") (pin "2") (pinfunction "2_2") (pintype "passive"))
      (node (ref "XI") (pin "9") (pinfunction "1_9") (pintype "passive"))
    )
    (net (code "58") (name "RAW") (class "Default")
      (node (ref "MC") (pin "RAW") (pinfunction "RAW_RAW") (pintype "power_in"))
    )
    (net (code "59") (name "RAW_IV") (class "Default")
      (node (ref "OD1") (pin "C") (pinfunction "C_C") (pintype "passive"))
      (node (ref "OD2") (pin "C") (pinfunction "C_C") (pintype "passive"))
      (node (ref "OD3") (pin "C") (pinfunction "C_C") (pintype "passive"))
      (node (ref "PC1") (pin "+") (pinfunction "+_+") (pintype "passive"))
      (node (ref "PF1") (pin "2") (pinfunction "2_2") (pintype "passive"))
      (node (ref "PIC33") (pin "1") (pinfunction "VIN_1") (pintype "input"))
      (node (ref "XI") (pin "1") (pinfunction "1_1") (pintype "passive"))
      (node (ref "XO") (pin "1") (pinfunction "1_1") (pintype "passive"))
      (node (ref "XO") (pin "3") (pinfunction "1_3") (pintype "passive"))
      (node (ref "XO") (pin "5") (pinfunction "1_5") (pintype "passive"))
    )
    (net (code "60") (name "RESET") (class "Default")
      (node (ref "C2") (pin "1") (pinfunction "1_1") (pintype "passive"))
      (node (ref "MC") (pin "RST$2") (pinfunction "RST$2_RST$2") (pintype "input"))
      (node (ref "R2") (pin "1") (pinfunction "1_1") (pintype "passive"))
      (node (ref "SR") (pin "1") (pinfunction "P_1") (pintype "passive"))
    )
    (net (code "61") (name "RXI") (class "Default")
      (node (ref "MC") (pin "RX1$1") (pinfunction "RX1$1_RX1$1") (pintype "bidirectional"))
      (node (ref "PP") (pin "4") (pinfunction "S_4") (pintype "passive"))
    )
    (net (code "62") (name "TXO") (class "Default")
      (node (ref "MC") (pin "TX0$1") (pinfunction "TX0$1_TX0$1") (pintype "bidirectional"))
      (node (ref "PP") (pin "3") (pinfunction "S_3") (pintype "passive"))
    )
    (net (code "63") (name "unconnected-(ENC-CLKOUT-Pad3)") (class "Default")
      (node (ref "ENC") (pin "3") (pinfunction "CLKOUT_3") (pintype "output"))
    )
    (net (code "64") (name "unconnected-(ENC-WOL-Pad5)") (class "Default")
      (node (ref "ENC") (pin "5") (pinfunction "WOL_5") (pintype "output"))
    )
    (net (code "65") (name "unconnected-(MC-PadRST$1)") (class "Default")
      (node (ref "MC") (pin "RST$1") (pinfunction "RST$1_RST$1") (pintype "input"))
    )
    (net (code "66") (name "unconnected-(PJ1-GND-PadP$4)") (class "Default")
      (node (ref "PJ1") (pin "P$4") (pinfunction "GND_P$4") (pintype "bidirectional"))
    )
    (net (code "67") (name "unconnected-(U$2-PadNC)") (class "Default")
      (node (ref "U$2") (pin "NC") (pinfunction "NC_NC") (pintype "bidirectional"))
    )
    (net (code "68") (name "unconnected-(WIFI-PadGPIO0)") (class "Default")
      (node (ref "WIFI") (pin "GPIO0") (pinfunction "GPIO0_GPIO0") (pintype "bidirectional"))
    )
    (net (code "69") (name "unconnected-(WIFI-PadGPIO2)") (class "Default")
      (node (ref "WIFI") (pin "GPIO2") (pinfunction "GPIO2_GPIO2") (pintype "bidirectional"))
    )
    (net (code "70") (name "unconnected-(WIFI-PadRST)") (class "Default")
      (node (ref "WIFI") (pin "RST") (pinfunction "RST_RST") (pintype "bidirectional"))
    )
  )
)
